# lab_1_samarin_usb_rs485.net
KiCad netlist of a schematic drawn in Altium Designer
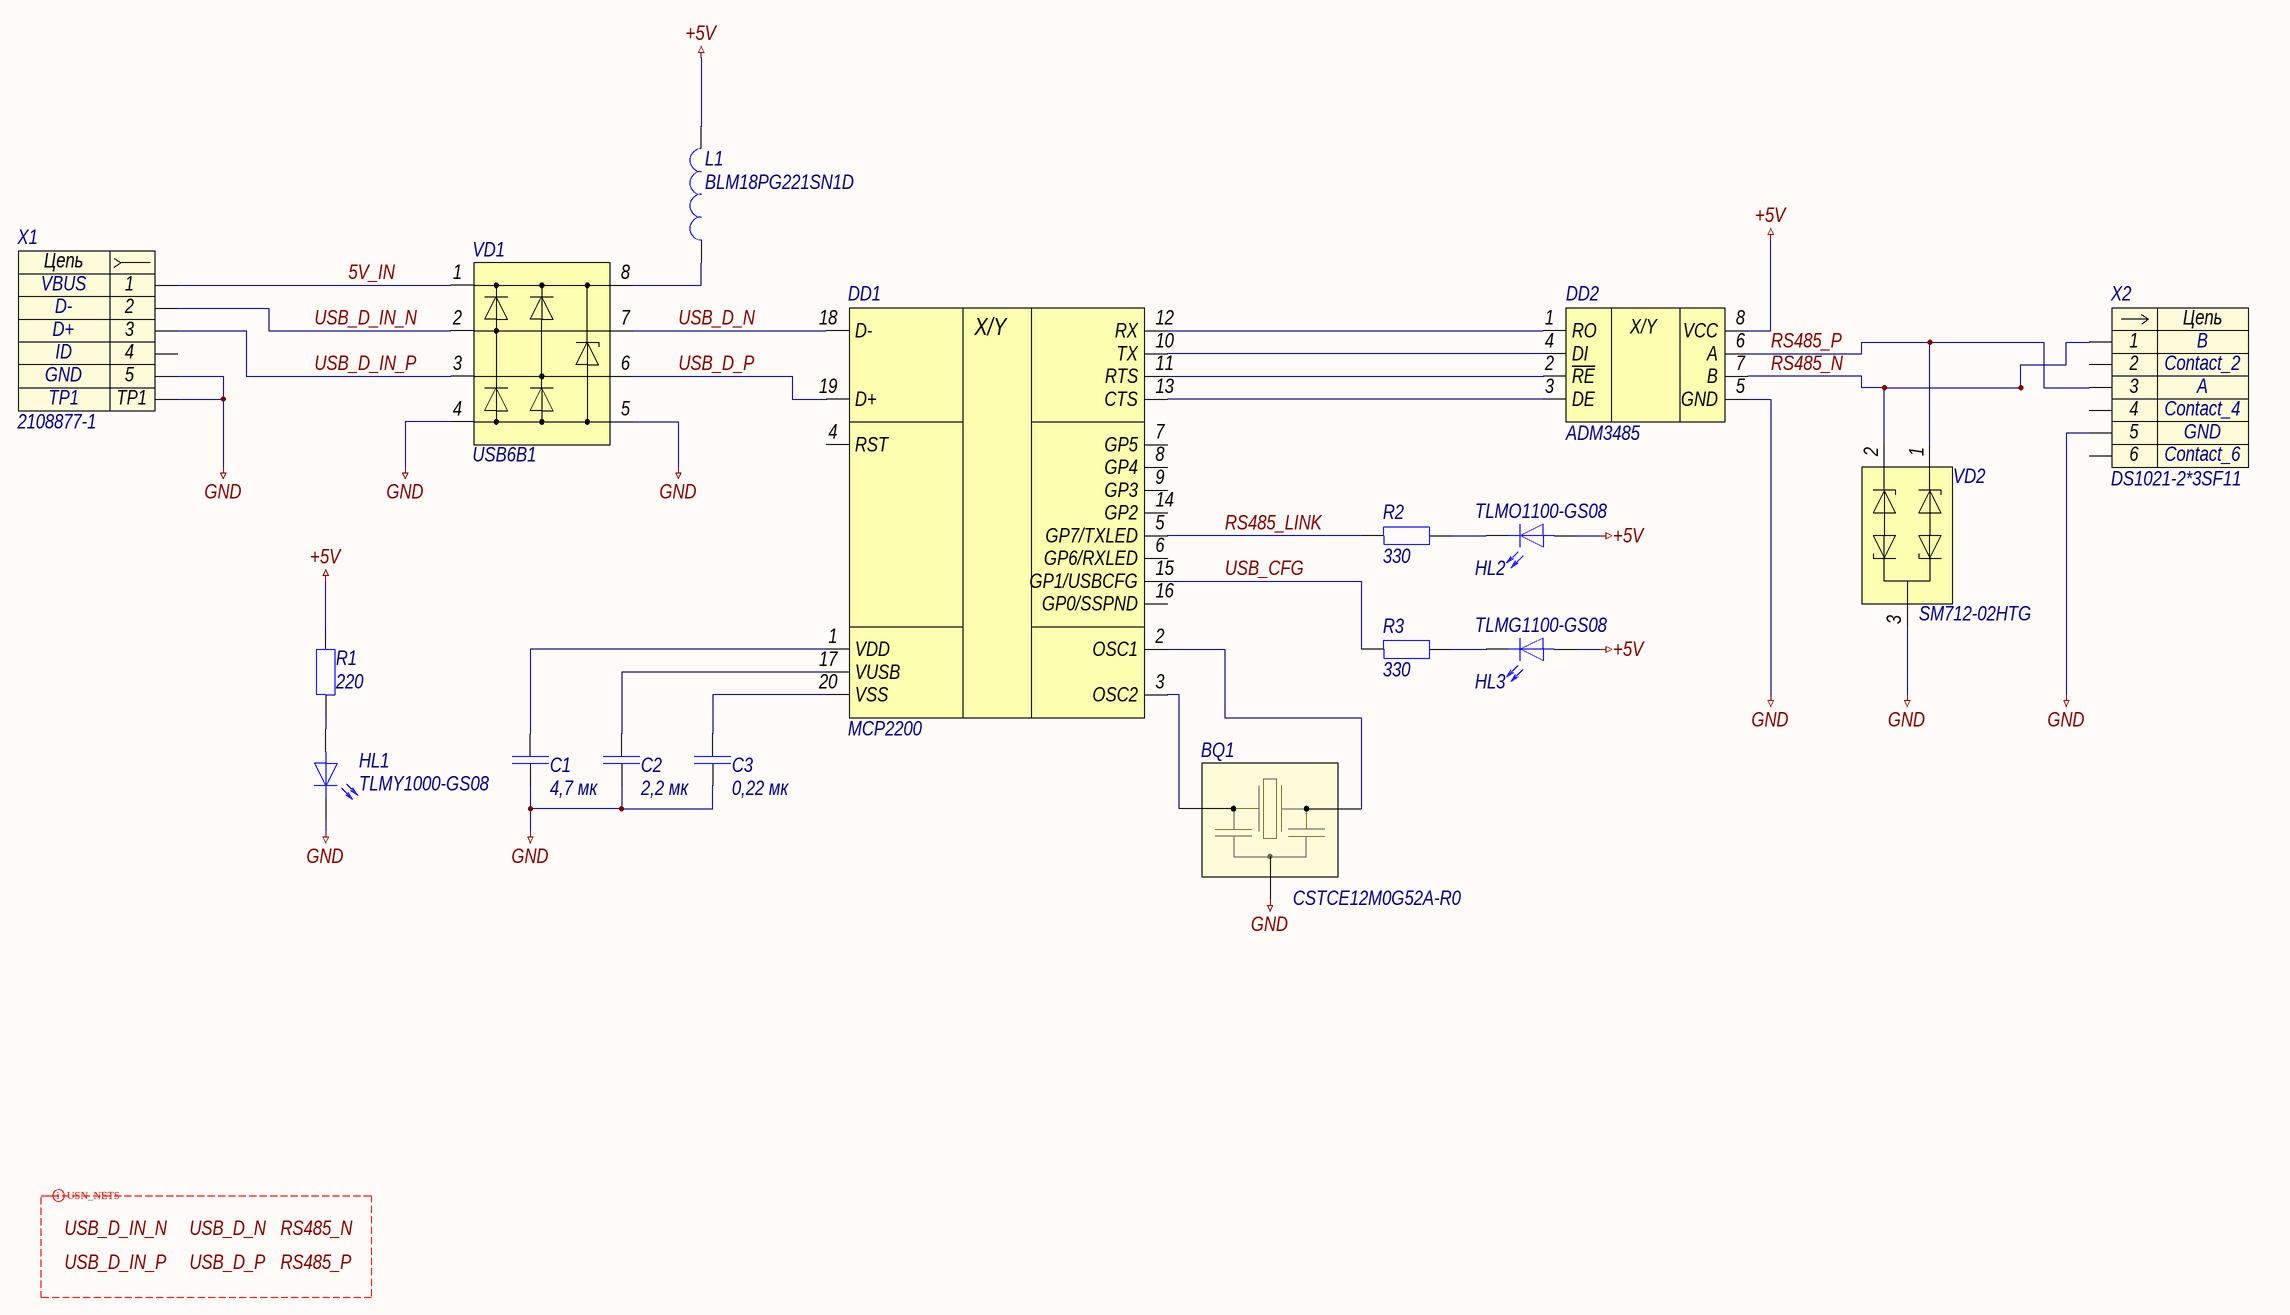
[diagram p0: lab_1_samarin_usb_rs485.SchDoc]

(export (version "E")
  (design (tool "Eeschema 10.0.6"))
  (components
    (comp (ref "BQ1")
      (value "CSTCE12M0G52A-R0")
      (footprint "CSTCE-3-320X130X40")
      (description "=Описание")
      (libsource (lib "Database_Students") (part "CSTCE12M0G52A-R0"))
    )
    (comp (ref "C1")
      (value "4,7 мк")
      (footprint "C0603")
      (description "=Описание")
      (libsource (lib "Database_Students") (part "C-NONPOLAR"))
    )
    (comp (ref "C2")
      (value "2,2 мк")
      (footprint "C0603")
      (description "=Описание")
      (libsource (lib "Database_Students") (part "C-NONPOLAR"))
    )
    (comp (ref "C3")
      (value "0,22 мк")
      (footprint "C0603")
      (description "=Описание")
      (libsource (lib "Database_Students") (part "C-NONPOLAR"))
    )
    (comp (ref "DD1")
      (value "MCP2200")
      (footprint "SOIC-20")
      (description "=Описание")
      (libsource (lib "Database_Students") (part "MCP2200"))
    )
    (comp (ref "DD2")
      (value "ADM3485")
      (footprint "SOIC-8")
      (description "=Описание")
      (libsource (lib "Database_Students") (part "ADM3485"))
    )
    (comp (ref "HL1")
      (value "TLMY1000-GS08")
      (footprint "HL0603")
      (description "=Описание")
      (libsource (lib "Database_Students") (part "HL-COMMON"))
    )
    (comp (ref "HL2")
      (value "TLMO1100-GS08")
      (footprint "HL0603")
      (description "=Описание")
      (libsource (lib "Database_Students") (part "HL-COMMON"))
    )
    (comp (ref "HL3")
      (value "TLMG1100-GS08")
      (footprint "HL0603")
      (description "=Описание")
      (libsource (lib "Database_Students") (part "HL-COMMON"))
    )
    (comp (ref "L1")
      (value "BLM18PG221SN1D")
      (footprint "BLM-2-0603")
      (description "=Описание")
      (libsource (lib "Database_Students") (part "FERRITE-BEAD"))
    )
    (comp (ref "R1")
      (value "220")
      (footprint "R0603")
      (description "=Описание")
      (libsource (lib "Database_Students") (part "R-COMMON"))
    )
    (comp (ref "R2")
      (value "330")
      (footprint "R0603")
      (description "=Описание")
      (libsource (lib "Database_Students") (part "R-COMMON"))
    )
    (comp (ref "R3")
      (value "330")
      (footprint "R0603")
      (description "=Описание")
      (libsource (lib "Database_Students") (part "R-COMMON"))
    )
    (comp (ref "VD1")
      (value "USB6B1")
      (footprint "SO-8")
      (description "=Описание")
      (libsource (lib "Database_Students") (part "USB6B1"))
    )
    (comp (ref "VD2")
      (value "SM712-02HTG")
      (footprint "SOT23-3")
      (description "=Описание")
      (libsource (lib "Database_Students") (part "SM712-02HTG"))
    )
    (comp (ref "X1")
      (value "2108877-1")
      (footprint "2108877-1")
      (libsource (lib "Database_Students") (part "HEADER-5-TP1-SCT"))
    )
    (comp (ref "X2")
      (value "DS1021-2*3SF11")
      (footprint "DS1021-2X3SF11")
      (libsource (lib "Database_Students") (part "HEADER-6-PLG"))
    )
  )
  (nets
    (net (code "1") (name "+5V") (class "Default")
      (node (ref "DD2") (pin "8") (pinfunction "VCC_8") (pintype "passive"))
      (node (ref "HL2") (pin "2") (pinfunction "2_2") (pintype "passive"))
      (node (ref "HL3") (pin "2") (pinfunction "2_2") (pintype "passive"))
      (node (ref "L1") (pin "2") (pinfunction "2_2") (pintype "passive"))
      (node (ref "R1") (pin "2") (pinfunction "2_2") (pintype "passive"))
    )
    (net (code "2") (name "/5V_IN") (class "Default")
      (node (ref "VD1") (pin "1") (pinfunction "1_1") (pintype "passive"))
      (node (ref "X1") (pin "1") (pinfunction "1_1") (pintype "passive"))
    )
    (net (code "3") (name "/RS485_LINK") (class "Default")
      (node (ref "DD1") (pin "5") (pinfunction "GP7/TXLED_5") (pintype "passive"))
      (node (ref "R2") (pin "1") (pinfunction "1_1") (pintype "passive"))
    )
    (net (code "4") (name "/RS485_N") (class "Default")
      (node (ref "DD2") (pin "7") (pinfunction "B_7") (pintype "passive"))
      (node (ref "VD2") (pin "2") (pinfunction "2_2") (pintype "passive"))
      (node (ref "X2") (pin "1") (pinfunction "1_1") (pintype "passive"))
    )
    (net (code "5") (name "/RS485_P") (class "Default")
      (node (ref "DD2") (pin "6") (pinfunction "A_6") (pintype "passive"))
      (node (ref "VD2") (pin "1") (pinfunction "1_1") (pintype "passive"))
      (node (ref "X2") (pin "3") (pinfunction "3_3") (pintype "passive"))
    )
    (net (code "6") (name "/USB_CFG") (class "Default")
      (node (ref "DD1") (pin "15") (pinfunction "GP1/USBCFG_15") (pintype "passive"))
      (node (ref "R3") (pin "1") (pinfunction "1_1") (pintype "passive"))
    )
    (net (code "7") (name "/USB_D_IN_N") (class "Default")
      (node (ref "VD1") (pin "2") (pinfunction "2_2") (pintype "passive"))
      (node (ref "X1") (pin "2") (pinfunction "2_2") (pintype "passive"))
    )
    (net (code "8") (name "/USB_D_IN_P") (class "Default")
      (node (ref "VD1") (pin "3") (pinfunction "3_3") (pintype "passive"))
      (node (ref "X1") (pin "3") (pinfunction "3_3") (pintype "passive"))
    )
    (net (code "9") (name "/USB_D_N") (class "Default")
      (node (ref "DD1") (pin "18") (pinfunction "D-_18") (pintype "passive"))
      (node (ref "VD1") (pin "7") (pinfunction "7_7") (pintype "passive"))
    )
    (net (code "10") (name "/USB_D_P") (class "Default")
      (node (ref "DD1") (pin "19") (pinfunction "D+_19") (pintype "passive"))
      (node (ref "VD1") (pin "6") (pinfunction "6_6") (pintype "passive"))
    )
    (net (code "11") (name "GND") (class "Default")
      (node (ref "BQ1") (pin "2") (pinfunction "2_2") (pintype "passive"))
      (node (ref "C1") (pin "1") (pinfunction "1_1") (pintype "passive"))
      (node (ref "C2") (pin "1") (pinfunction "1_1") (pintype "passive"))
      (node (ref "C3") (pin "1") (pinfunction "1_1") (pintype "passive"))
      (node (ref "DD2") (pin "5") (pinfunction "GND_5") (pintype "passive"))
      (node (ref "HL1") (pin "1") (pinfunction "1_1") (pintype "passive"))
      (node (ref "VD1") (pin "4") (pinfunction "4_4") (pintype "passive"))
      (node (ref "VD1") (pin "5") (pinfunction "5_5") (pintype "passive"))
      (node (ref "VD2") (pin "3") (pinfunction "3_3") (pintype "passive"))
      (node (ref "X1") (pin "5") (pinfunction "5_5") (pintype "passive"))
      (node (ref "X1") (pin "TP1") (pinfunction "TP1_TP1") (pintype "passive"))
      (node (ref "X2") (pin "5") (pinfunction "5_5") (pintype "passive"))
    )
    (net (code "12") (name "Net-(DD1-CTS)") (class "Default")
      (node (ref "DD1") (pin "13") (pinfunction "CTS_13") (pintype "passive"))
      (node (ref "DD2") (pin "3") (pinfunction "DE_3") (pintype "passive"))
    )
    (net (code "13") (name "Net-(DD1-OSC1)") (class "Default")
      (node (ref "BQ1") (pin "1") (pinfunction "1_1") (pintype "passive"))
      (node (ref "DD1") (pin "2") (pinfunction "OSC1_2") (pintype "passive"))
    )
    (net (code "14") (name "Net-(DD1-OSC2)") (class "Default")
      (node (ref "BQ1") (pin "3") (pinfunction "3_3") (pintype "passive"))
      (node (ref "DD1") (pin "3") (pinfunction "OSC2_3") (pintype "passive"))
    )
    (net (code "15") (name "Net-(DD1-RTS)") (class "Default")
      (node (ref "DD1") (pin "11") (pinfunction "RTS_11") (pintype "passive"))
      (node (ref "DD2") (pin "2") (pinfunction "~{RE}_2") (pintype "passive"))
    )
    (net (code "16") (name "Net-(DD1-RX)") (class "Default")
      (node (ref "DD1") (pin "12") (pinfunction "RX_12") (pintype "passive"))
      (node (ref "DD2") (pin "1") (pinfunction "RO_1") (pintype "passive"))
    )
    (net (code "17") (name "Net-(DD1-TX)") (class "Default")
      (node (ref "DD1") (pin "10") (pinfunction "TX_10") (pintype "passive"))
      (node (ref "DD2") (pin "4") (pinfunction "DI_4") (pintype "passive"))
    )
    (net (code "18") (name "Net-(DD1-VDD)") (class "Default")
      (node (ref "C1") (pin "2") (pinfunction "2_2") (pintype "passive"))
      (node (ref "DD1") (pin "1") (pinfunction "VDD_1") (pintype "passive"))
    )
    (net (code "19") (name "Net-(DD1-VSS)") (class "Default")
      (node (ref "C3") (pin "2") (pinfunction "2_2") (pintype "passive"))
      (node (ref "DD1") (pin "20") (pinfunction "VSS_20") (pintype "passive"))
    )
    (net (code "20") (name "Net-(DD1-VUSB)") (class "Default")
      (node (ref "C2") (pin "2") (pinfunction "2_2") (pintype "passive"))
      (node (ref "DD1") (pin "17") (pinfunction "VUSB_17") (pintype "passive"))
    )
    (net (code "21") (name "Net-(HL1-Pad2)") (class "Default")
      (node (ref "HL1") (pin "2") (pinfunction "2_2") (pintype "passive"))
      (node (ref "R1") (pin "1") (pinfunction "1_1") (pintype "passive"))
    )
    (net (code "22") (name "Net-(HL2-Pad1)") (class "Default")
      (node (ref "HL2") (pin "1") (pinfunction "1_1") (pintype "passive"))
      (node (ref "R2") (pin "2") (pinfunction "2_2") (pintype "passive"))
    )
    (net (code "23") (name "Net-(HL3-Pad1)") (class "Default")
      (node (ref "HL3") (pin "1") (pinfunction "1_1") (pintype "passive"))
      (node (ref "R3") (pin "2") (pinfunction "2_2") (pintype "passive"))
    )
    (net (code "24") (name "Net-(L1-Pad1)") (class "Default")
      (node (ref "L1") (pin "1") (pinfunction "1_1") (pintype "passive"))
      (node (ref "VD1") (pin "8") (pinfunction "8_8") (pintype "passive"))
    )
    (net (code "25") (name "unconnected-(DD1-GP0{slash}SSPND-Pad16)") (class "Default")
      (node (ref "DD1") (pin "16") (pinfunction "GP0/SSPND_16") (pintype "passive"))
    )
    (net (code "26") (name "unconnected-(DD1-GP2-Pad14)") (class "Default")
      (node (ref "DD1") (pin "14") (pinfunction "GP2_14") (pintype "passive"))
    )
    (net (code "27") (name "unconnected-(DD1-GP3-Pad9)") (class "Default")
      (node (ref "DD1") (pin "9") (pinfunction "GP3_9") (pintype "passive"))
    )
    (net (code "28") (name "unconnected-(DD1-GP4-Pad8)") (class "Default")
      (node (ref "DD1") (pin "8") (pinfunction "GP4_8") (pintype "passive"))
    )
    (net (code "29") (name "unconnected-(DD1-GP5-Pad7)") (class "Default")
      (node (ref "DD1") (pin "7") (pinfunction "GP5_7") (pintype "passive"))
    )
    (net (code "30") (name "unconnected-(DD1-GP6{slash}RXLED-Pad6)") (class "Default")
      (node (ref "DD1") (pin "6") (pinfunction "GP6/RXLED_6") (pintype "passive"))
    )
    (net (code "31") (name "unconnected-(DD1-RST-Pad4)") (class "Default")
      (node (ref "DD1") (pin "4") (pinfunction "RST_4") (pintype "passive"))
    )
    (net (code "32") (name "unconnected-(X1-Pad4)") (class "Default")
      (node (ref "X1") (pin "4") (pinfunction "4_4") (pintype "passive"))
    )
    (net (code "33") (name "unconnected-(X2-Pad2)") (class "Default")
      (node (ref "X2") (pin "2") (pinfunction "2_2") (pintype "passive"))
    )
    (net (code "34") (name "unconnected-(X2-Pad4)") (class "Default")
      (node (ref "X2") (pin "4") (pinfunction "4_4") (pintype "passive"))
    )
    (net (code "35") (name "unconnected-(X2-Pad6)") (class "Default")
      (node (ref "X2") (pin "6") (pinfunction "6_6") (pintype "passive"))
    )
  )
)
